# APP_1_DDR3_m.net
KiCad netlist of a schematic drawn in Altium Designer
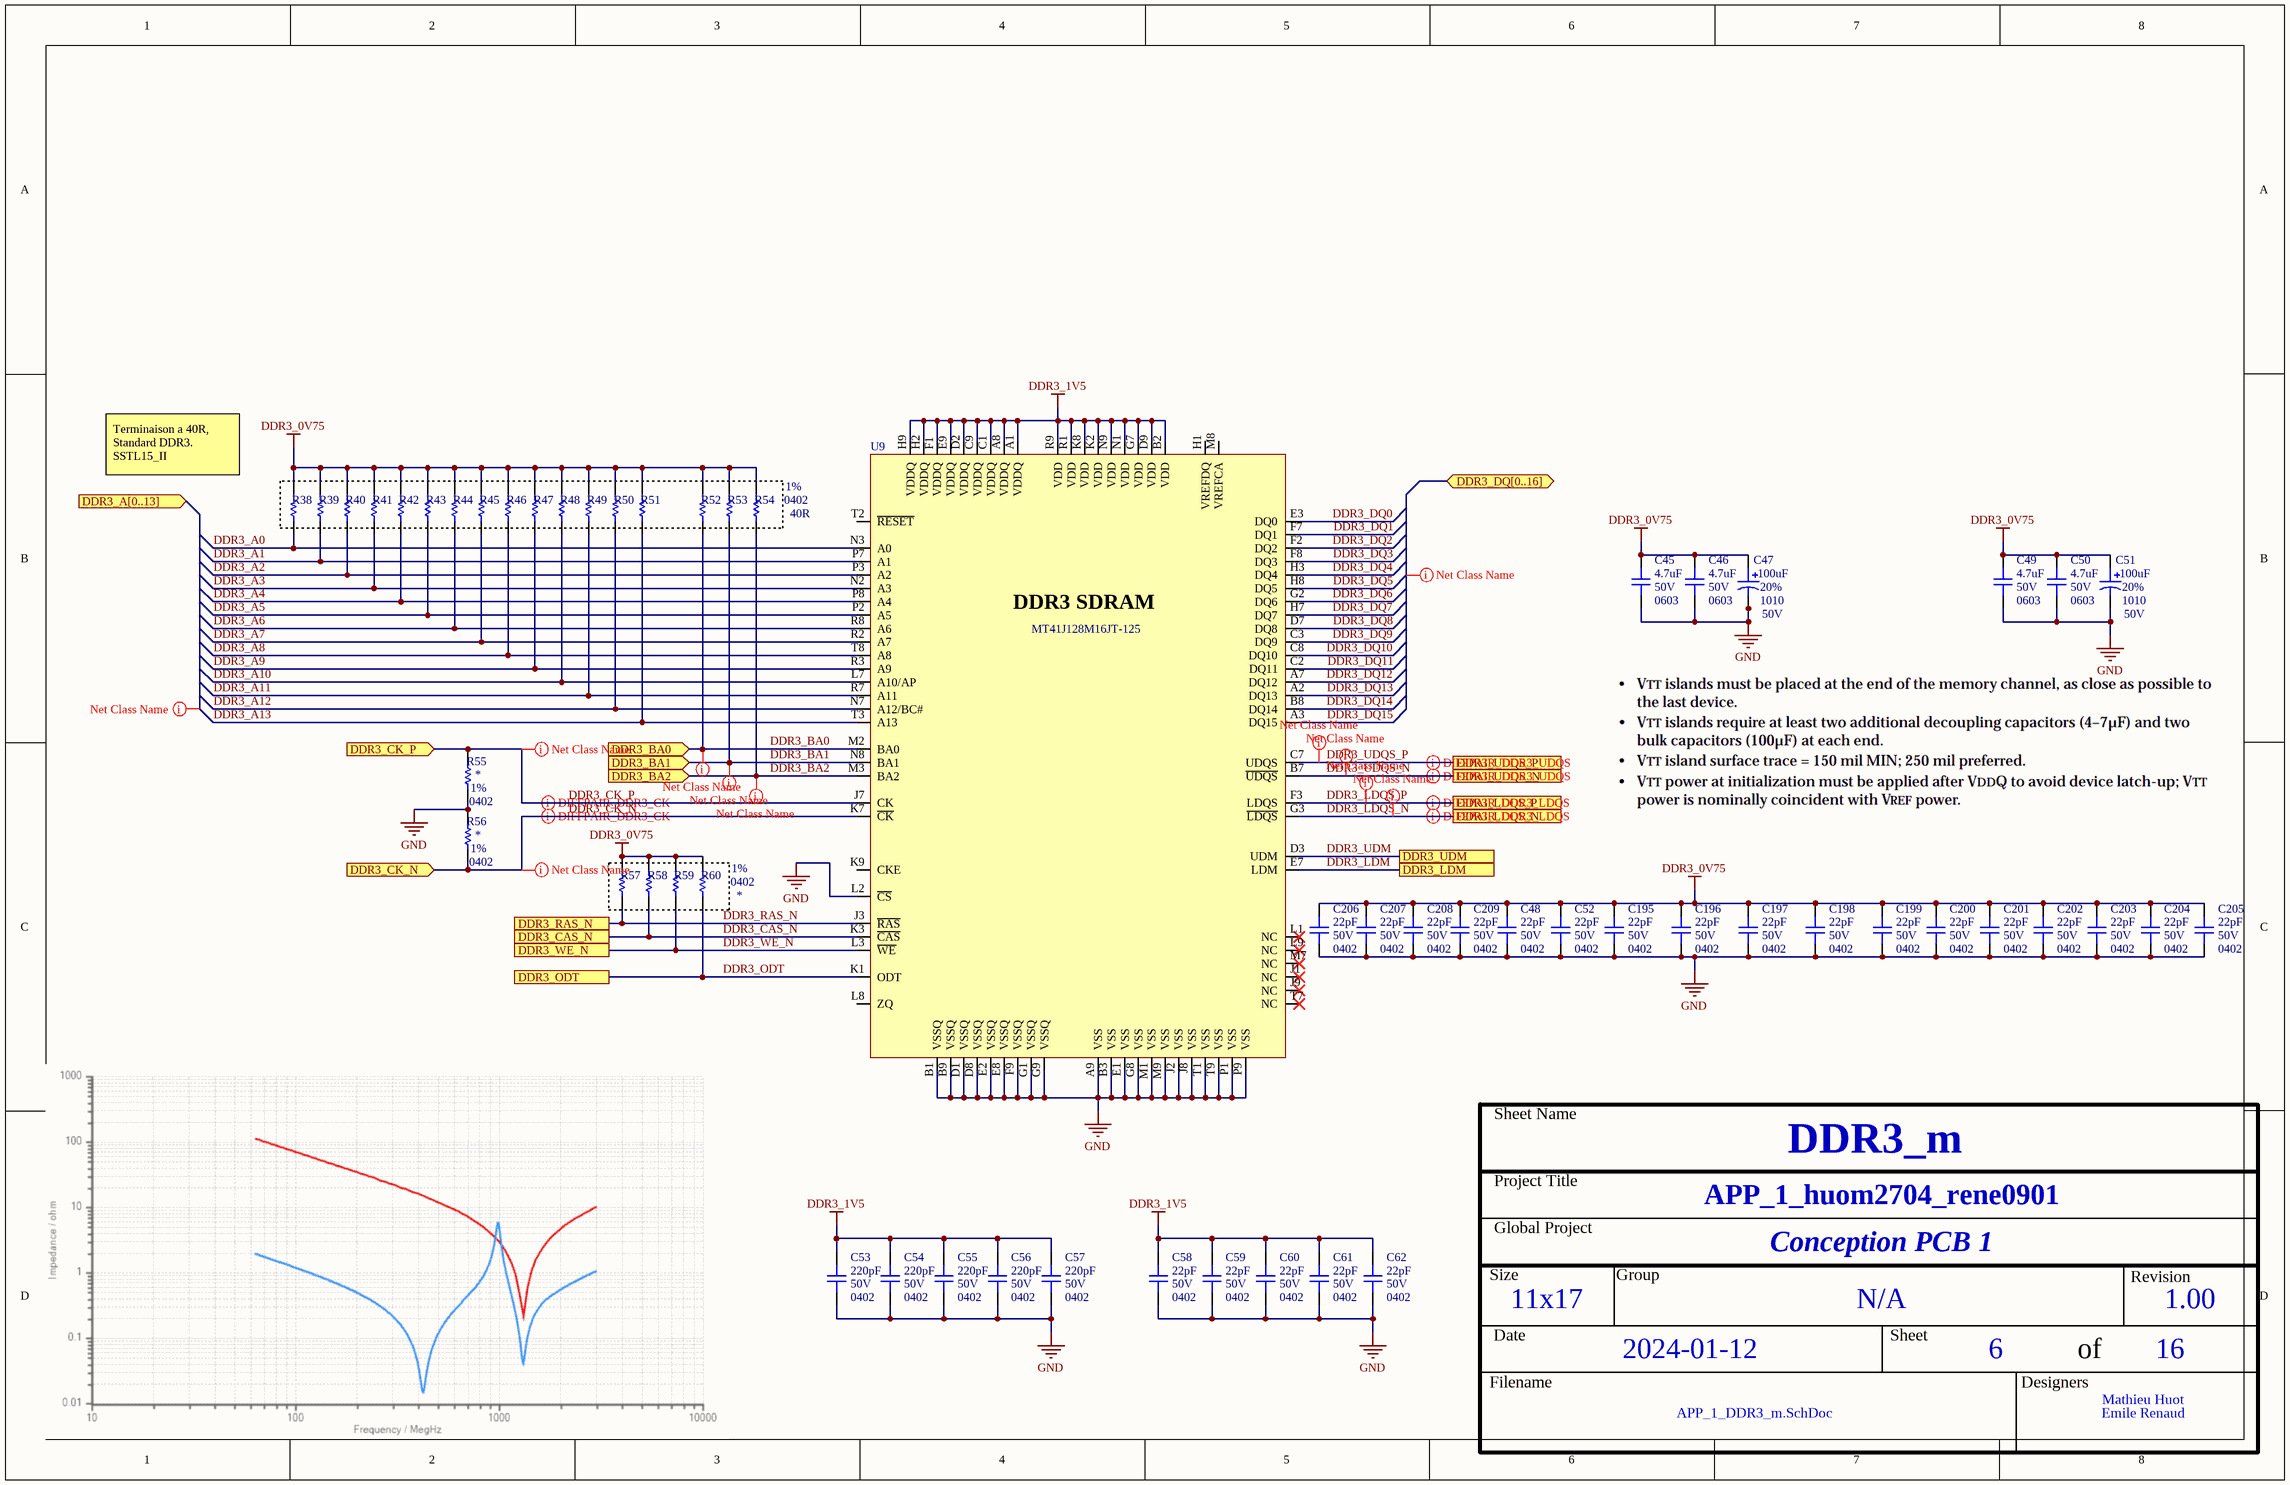
[diagram p0: APP_1_DDR3_m.SchDoc]

(export (version "E")
  (design (tool "Eeschema 10.0.6"))
  (components
    (comp (ref "C45")
      (value "4.7uF")
      (footprint "CAP_0603")
      (description "CAP - 0603")
      (fields
        (field (name "VOLTAGE") "50V")
        (field (name "PACKAGE") "0603")
        (field (name "CREATEDBY") "Jonathan Bouchard")
      )
      (libsource (lib "S7CAS_LIB2023") (part "CAP - 0603"))
    )
    (comp (ref "C46")
      (value "4.7uF")
      (footprint "CAP_0603")
      (description "CAP - 0603")
      (fields
        (field (name "VOLTAGE") "50V")
        (field (name "PACKAGE") "0603")
        (field (name "CREATEDBY") "Jonathan Bouchard")
      )
      (libsource (lib "S7CAS_LIB2023") (part "CAP - 0603"))
    )
    (comp (ref "C47")
      (value "100uF")
      (footprint "CAP_ALU_1010_vishay")
      (description "CAP - ALU 100uF 20% 50V - 1010")
      (fields
        (field (name "MFG") "Vishay Dale")
        (field (name "MFG PART NUMBER") "MAL215099101E3")
        (field (name "VOLTAGE") "50V")
        (field (name "PACKAGE") "1010")
        (field (name "PRECISION") "20%")
        (field (name "CREATEDBY") "Jonathan Bouchard")
      )
      (libsource (lib "S7CAS_LIB2023") (part "CAP_ALU_MAL215099101E3"))
    )
    (comp (ref "C48")
      (value "22pF")
      (footprint "CAP_0402")
      (description "CAP - 0402")
      (fields
        (field (name "VOLTAGE") "50V")
        (field (name "PACKAGE") "0402")
        (field (name "CREATEDBY") "Jonathan Bouchard")
      )
      (libsource (lib "S7CAS_LIB2023") (part "CAP - 0402"))
    )
    (comp (ref "C49")
      (value "4.7uF")
      (footprint "CAP_0603")
      (description "CAP - 0603")
      (fields
        (field (name "VOLTAGE") "50V")
        (field (name "PACKAGE") "0603")
        (field (name "CREATEDBY") "Jonathan Bouchard")
      )
      (libsource (lib "S7CAS_LIB2023") (part "CAP - 0603"))
    )
    (comp (ref "C50")
      (value "4.7uF")
      (footprint "CAP_0603")
      (description "CAP - 0603")
      (fields
        (field (name "VOLTAGE") "50V")
        (field (name "PACKAGE") "0603")
        (field (name "CREATEDBY") "Jonathan Bouchard")
      )
      (libsource (lib "S7CAS_LIB2023") (part "CAP - 0603"))
    )
    (comp (ref "C51")
      (value "100uF")
      (footprint "CAP_ALU_1010_vishay")
      (description "CAP - ALU 100uF 20% 50V - 1010")
      (fields
        (field (name "MFG") "Vishay Dale")
        (field (name "MFG PART NUMBER") "MAL215099101E3")
        (field (name "VOLTAGE") "50V")
        (field (name "PACKAGE") "1010")
        (field (name "PRECISION") "20%")
        (field (name "CREATEDBY") "Jonathan Bouchard")
      )
      (libsource (lib "S7CAS_LIB2023") (part "CAP_ALU_MAL215099101E3"))
    )
    (comp (ref "C52")
      (value "22pF")
      (footprint "CAP_0402")
      (description "CAP - 0402")
      (fields
        (field (name "VOLTAGE") "50V")
        (field (name "PACKAGE") "0402")
        (field (name "CREATEDBY") "Jonathan Bouchard")
      )
      (libsource (lib "S7CAS_LIB2023") (part "CAP - 0402"))
    )
    (comp (ref "C53")
      (value "220pF")
      (footprint "CAP_0402")
      (description "CAP - 0402")
      (fields
        (field (name "VOLTAGE") "50V")
        (field (name "PACKAGE") "0402")
        (field (name "CREATEDBY") "Jonathan Bouchard")
      )
      (libsource (lib "S7CAS_LIB2023") (part "CAP - 0402"))
    )
    (comp (ref "C54")
      (value "220pF")
      (footprint "CAP_0402")
      (description "CAP - 0402")
      (fields
        (field (name "VOLTAGE") "50V")
        (field (name "PACKAGE") "0402")
        (field (name "CREATEDBY") "Jonathan Bouchard")
      )
      (libsource (lib "S7CAS_LIB2023") (part "CAP - 0402"))
    )
    (comp (ref "C55")
      (value "220pF")
      (footprint "CAP_0402")
      (description "CAP - 0402")
      (fields
        (field (name "VOLTAGE") "50V")
        (field (name "PACKAGE") "0402")
        (field (name "CREATEDBY") "Jonathan Bouchard")
      )
      (libsource (lib "S7CAS_LIB2023") (part "CAP - 0402"))
    )
    (comp (ref "C56")
      (value "220pF")
      (footprint "CAP_0402")
      (description "CAP - 0402")
      (fields
        (field (name "VOLTAGE") "50V")
        (field (name "PACKAGE") "0402")
        (field (name "CREATEDBY") "Jonathan Bouchard")
      )
      (libsource (lib "S7CAS_LIB2023") (part "CAP - 0402"))
    )
    (comp (ref "C57")
      (value "220pF")
      (footprint "CAP_0402")
      (description "CAP - 0402")
      (fields
        (field (name "VOLTAGE") "50V")
        (field (name "PACKAGE") "0402")
        (field (name "CREATEDBY") "Jonathan Bouchard")
      )
      (libsource (lib "S7CAS_LIB2023") (part "CAP - 0402"))
    )
    (comp (ref "C58")
      (value "22pF")
      (footprint "CAP_0402")
      (description "CAP - 0402")
      (fields
        (field (name "VOLTAGE") "50V")
        (field (name "PACKAGE") "0402")
        (field (name "CREATEDBY") "Jonathan Bouchard")
      )
      (libsource (lib "S7CAS_LIB2023") (part "CAP - 0402"))
    )
    (comp (ref "C59")
      (value "22pF")
      (footprint "CAP_0402")
      (description "CAP - 0402")
      (fields
        (field (name "VOLTAGE") "50V")
        (field (name "PACKAGE") "0402")
        (field (name "CREATEDBY") "Jonathan Bouchard")
      )
      (libsource (lib "S7CAS_LIB2023") (part "CAP - 0402"))
    )
    (comp (ref "C60")
      (value "22pF")
      (footprint "CAP_0402")
      (description "CAP - 0402")
      (fields
        (field (name "VOLTAGE") "50V")
        (field (name "PACKAGE") "0402")
        (field (name "CREATEDBY") "Jonathan Bouchard")
      )
      (libsource (lib "S7CAS_LIB2023") (part "CAP - 0402"))
    )
    (comp (ref "C61")
      (value "22pF")
      (footprint "CAP_0402")
      (description "CAP - 0402")
      (fields
        (field (name "VOLTAGE") "50V")
        (field (name "PACKAGE") "0402")
        (field (name "CREATEDBY") "Jonathan Bouchard")
      )
      (libsource (lib "S7CAS_LIB2023") (part "CAP - 0402"))
    )
    (comp (ref "C62")
      (value "22pF")
      (footprint "CAP_0402")
      (description "CAP - 0402")
      (fields
        (field (name "VOLTAGE") "50V")
        (field (name "PACKAGE") "0402")
        (field (name "CREATEDBY") "Jonathan Bouchard")
      )
      (libsource (lib "S7CAS_LIB2023") (part "CAP - 0402"))
    )
    (comp (ref "C195")
      (value "22pF")
      (footprint "CAP_0402")
      (description "CAP - 0402")
      (fields
        (field (name "VOLTAGE") "50V")
        (field (name "PACKAGE") "0402")
        (field (name "CREATEDBY") "Jonathan Bouchard")
      )
      (libsource (lib "S7CAS_LIB2023") (part "CAP - 0402"))
    )
    (comp (ref "C196")
      (value "22pF")
      (footprint "CAP_0402")
      (description "CAP - 0402")
      (fields
        (field (name "VOLTAGE") "50V")
        (field (name "PACKAGE") "0402")
        (field (name "CREATEDBY") "Jonathan Bouchard")
      )
      (libsource (lib "S7CAS_LIB2023") (part "CAP - 0402"))
    )
    (comp (ref "C197")
      (value "22pF")
      (footprint "CAP_0402")
      (description "CAP - 0402")
      (fields
        (field (name "VOLTAGE") "50V")
        (field (name "PACKAGE") "0402")
        (field (name "CREATEDBY") "Jonathan Bouchard")
      )
      (libsource (lib "S7CAS_LIB2023") (part "CAP - 0402"))
    )
    (comp (ref "C198")
      (value "22pF")
      (footprint "CAP_0402")
      (description "CAP - 0402")
      (fields
        (field (name "VOLTAGE") "50V")
        (field (name "PACKAGE") "0402")
        (field (name "CREATEDBY") "Jonathan Bouchard")
      )
      (libsource (lib "S7CAS_LIB2023") (part "CAP - 0402"))
    )
    (comp (ref "C199")
      (value "22pF")
      (footprint "CAP_0402")
      (description "CAP - 0402")
      (fields
        (field (name "VOLTAGE") "50V")
        (field (name "PACKAGE") "0402")
        (field (name "CREATEDBY") "Jonathan Bouchard")
      )
      (libsource (lib "S7CAS_LIB2023") (part "CAP - 0402"))
    )
    (comp (ref "C200")
      (value "22pF")
      (footprint "CAP_0402")
      (description "CAP - 0402")
      (fields
        (field (name "VOLTAGE") "50V")
        (field (name "PACKAGE") "0402")
        (field (name "CREATEDBY") "Jonathan Bouchard")
      )
      (libsource (lib "S7CAS_LIB2023") (part "CAP - 0402"))
    )
    (comp (ref "C201")
      (value "22pF")
      (footprint "CAP_0402")
      (description "CAP - 0402")
      (fields
        (field (name "VOLTAGE") "50V")
        (field (name "PACKAGE") "0402")
        (field (name "CREATEDBY") "Jonathan Bouchard")
      )
      (libsource (lib "S7CAS_LIB2023") (part "CAP - 0402"))
    )
    (comp (ref "C202")
      (value "22pF")
      (footprint "CAP_0402")
      (description "CAP - 0402")
      (fields
        (field (name "VOLTAGE") "50V")
        (field (name "PACKAGE") "0402")
        (field (name "CREATEDBY") "Jonathan Bouchard")
      )
      (libsource (lib "S7CAS_LIB2023") (part "CAP - 0402"))
    )
    (comp (ref "C203")
      (value "22pF")
      (footprint "CAP_0402")
      (description "CAP - 0402")
      (fields
        (field (name "VOLTAGE") "50V")
        (field (name "PACKAGE") "0402")
        (field (name "CREATEDBY") "Jonathan Bouchard")
      )
      (libsource (lib "S7CAS_LIB2023") (part "CAP - 0402"))
    )
    (comp (ref "C204")
      (value "22pF")
      (footprint "CAP_0402")
      (description "CAP - 0402")
      (fields
        (field (name "VOLTAGE") "50V")
        (field (name "PACKAGE") "0402")
        (field (name "CREATEDBY") "Jonathan Bouchard")
      )
      (libsource (lib "S7CAS_LIB2023") (part "CAP - 0402"))
    )
    (comp (ref "C205")
      (value "22pF")
      (footprint "CAP_0402")
      (description "CAP - 0402")
      (fields
        (field (name "VOLTAGE") "50V")
        (field (name "PACKAGE") "0402")
        (field (name "CREATEDBY") "Jonathan Bouchard")
      )
      (libsource (lib "S7CAS_LIB2023") (part "CAP - 0402"))
    )
    (comp (ref "C206")
      (value "22pF")
      (footprint "CAP_0402")
      (description "CAP - 0402")
      (fields
        (field (name "VOLTAGE") "50V")
        (field (name "PACKAGE") "0402")
        (field (name "CREATEDBY") "Jonathan Bouchard")
      )
      (libsource (lib "S7CAS_LIB2023") (part "CAP - 0402"))
    )
    (comp (ref "C207")
      (value "22pF")
      (footprint "CAP_0402")
      (description "CAP - 0402")
      (fields
        (field (name "VOLTAGE") "50V")
        (field (name "PACKAGE") "0402")
        (field (name "CREATEDBY") "Jonathan Bouchard")
      )
      (libsource (lib "S7CAS_LIB2023") (part "CAP - 0402"))
    )
    (comp (ref "C208")
      (value "22pF")
      (footprint "CAP_0402")
      (description "CAP - 0402")
      (fields
        (field (name "VOLTAGE") "50V")
        (field (name "PACKAGE") "0402")
        (field (name "CREATEDBY") "Jonathan Bouchard")
      )
      (libsource (lib "S7CAS_LIB2023") (part "CAP - 0402"))
    )
    (comp (ref "C209")
      (value "22pF")
      (footprint "CAP_0402")
      (description "CAP - 0402")
      (fields
        (field (name "VOLTAGE") "50V")
        (field (name "PACKAGE") "0402")
        (field (name "CREATEDBY") "Jonathan Bouchard")
      )
      (libsource (lib "S7CAS_LIB2023") (part "CAP - 0402"))
    )
    (comp (ref "R38")
      (value "RES - 0402")
      (footprint "RES_0402")
      (fields
        (field (name "VOLTAGE") "50V")
        (field (name "POWER") "1/16W")
        (field (name "CREATEDBY") "Jonathan Bouchard")
      )
      (libsource (lib "S7CAS_LIB2023") (part "RES - 0402"))
    )
    (comp (ref "R39")
      (value "RES - 0402")
      (footprint "RES_0402")
      (fields
        (field (name "VOLTAGE") "50V")
        (field (name "POWER") "1/16W")
        (field (name "CREATEDBY") "Jonathan Bouchard")
      )
      (libsource (lib "S7CAS_LIB2023") (part "RES - 0402"))
    )
    (comp (ref "R40")
      (value "RES - 0402")
      (footprint "RES_0402")
      (fields
        (field (name "VOLTAGE") "50V")
        (field (name "POWER") "1/16W")
        (field (name "CREATEDBY") "Jonathan Bouchard")
      )
      (libsource (lib "S7CAS_LIB2023") (part "RES - 0402"))
    )
    (comp (ref "R41")
      (value "RES - 0402")
      (footprint "RES_0402")
      (fields
        (field (name "VOLTAGE") "50V")
        (field (name "POWER") "1/16W")
        (field (name "CREATEDBY") "Jonathan Bouchard")
      )
      (libsource (lib "S7CAS_LIB2023") (part "RES - 0402"))
    )
    (comp (ref "R42")
      (value "RES - 0402")
      (footprint "RES_0402")
      (fields
        (field (name "VOLTAGE") "50V")
        (field (name "POWER") "1/16W")
        (field (name "CREATEDBY") "Jonathan Bouchard")
      )
      (libsource (lib "S7CAS_LIB2023") (part "RES - 0402"))
    )
    (comp (ref "R43")
      (value "RES - 0402")
      (footprint "RES_0402")
      (fields
        (field (name "VOLTAGE") "50V")
        (field (name "POWER") "1/16W")
        (field (name "CREATEDBY") "Jonathan Bouchard")
      )
      (libsource (lib "S7CAS_LIB2023") (part "RES - 0402"))
    )
    (comp (ref "R44")
      (value "RES - 0402")
      (footprint "RES_0402")
      (fields
        (field (name "VOLTAGE") "50V")
        (field (name "POWER") "1/16W")
        (field (name "CREATEDBY") "Jonathan Bouchard")
      )
      (libsource (lib "S7CAS_LIB2023") (part "RES - 0402"))
    )
    (comp (ref "R45")
      (value "RES - 0402")
      (footprint "RES_0402")
      (fields
        (field (name "VOLTAGE") "50V")
        (field (name "POWER") "1/16W")
        (field (name "CREATEDBY") "Jonathan Bouchard")
      )
      (libsource (lib "S7CAS_LIB2023") (part "RES - 0402"))
    )
    (comp (ref "R46")
      (value "RES - 0402")
      (footprint "RES_0402")
      (fields
        (field (name "VOLTAGE") "50V")
        (field (name "POWER") "1/16W")
        (field (name "CREATEDBY") "Jonathan Bouchard")
      )
      (libsource (lib "S7CAS_LIB2023") (part "RES - 0402"))
    )
    (comp (ref "R47")
      (value "RES - 0402")
      (footprint "RES_0402")
      (fields
        (field (name "VOLTAGE") "50V")
        (field (name "POWER") "1/16W")
        (field (name "CREATEDBY") "Jonathan Bouchard")
      )
      (libsource (lib "S7CAS_LIB2023") (part "RES - 0402"))
    )
    (comp (ref "R48")
      (value "RES - 0402")
      (footprint "RES_0402")
      (fields
        (field (name "VOLTAGE") "50V")
        (field (name "POWER") "1/16W")
        (field (name "CREATEDBY") "Jonathan Bouchard")
      )
      (libsource (lib "S7CAS_LIB2023") (part "RES - 0402"))
    )
    (comp (ref "R49")
      (value "RES - 0402")
      (footprint "RES_0402")
      (fields
        (field (name "VOLTAGE") "50V")
        (field (name "POWER") "1/16W")
        (field (name "CREATEDBY") "Jonathan Bouchard")
      )
      (libsource (lib "S7CAS_LIB2023") (part "RES - 0402"))
    )
    (comp (ref "R50")
      (value "RES - 0402")
      (footprint "RES_0402")
      (fields
        (field (name "VOLTAGE") "50V")
        (field (name "POWER") "1/16W")
        (field (name "CREATEDBY") "Jonathan Bouchard")
      )
      (libsource (lib "S7CAS_LIB2023") (part "RES - 0402"))
    )
    (comp (ref "R51")
      (value "RES - 0402")
      (footprint "RES_0402")
      (fields
        (field (name "VOLTAGE") "50V")
        (field (name "POWER") "1/16W")
        (field (name "CREATEDBY") "Jonathan Bouchard")
      )
      (libsource (lib "S7CAS_LIB2023") (part "RES - 0402"))
    )
    (comp (ref "R52")
      (value "RES - 0402")
      (footprint "RES_0402")
      (fields
        (field (name "VOLTAGE") "50V")
        (field (name "POWER") "1/16W")
        (field (name "CREATEDBY") "Jonathan Bouchard")
      )
      (libsource (lib "S7CAS_LIB2023") (part "RES - 0402"))
    )
    (comp (ref "R53")
      (value "RES - 0402")
      (footprint "RES_0402")
      (fields
        (field (name "VOLTAGE") "50V")
        (field (name "POWER") "1/16W")
        (field (name "CREATEDBY") "Jonathan Bouchard")
      )
      (libsource (lib "S7CAS_LIB2023") (part "RES - 0402"))
    )
    (comp (ref "R54")
      (value "40R")
      (footprint "RES_0402")
      (description "RES - 0402")
      (fields
        (field (name "VOLTAGE") "50V")
        (field (name "POWER") "1/16W")
        (field (name "PACKAGE") "0402")
        (field (name "PRECISION") "1%")
        (field (name "CREATEDBY") "Jonathan Bouchard")
      )
      (libsource (lib "S7CAS_LIB2023") (part "RES - 0402"))
    )
    (comp (ref "R55")
      (value "RES - 0402")
      (footprint "RES_0402")
      (fields
        (field (name "VOLTAGE") "50V")
        (field (name "POWER") "1/16W")
        (field (name "PACKAGE") "0402")
        (field (name "PRECISION") "1%")
        (field (name "ALTIUM_VALUE") "*")
        (field (name "CREATEDBY") "Jonathan Bouchard")
      )
      (libsource (lib "S7CAS_LIB2023") (part "RES - 0402"))
    )
    (comp (ref "R56")
      (value "RES - 0402")
      (footprint "RES_0402")
      (fields
        (field (name "VOLTAGE") "50V")
        (field (name "POWER") "1/16W")
        (field (name "PACKAGE") "0402")
        (field (name "PRECISION") "1%")
        (field (name "ALTIUM_VALUE") "*")
        (field (name "CREATEDBY") "Jonathan Bouchard")
      )
      (libsource (lib "S7CAS_LIB2023") (part "RES - 0402"))
    )
    (comp (ref "R57")
      (value "RES - 0402")
      (footprint "RES_0402")
      (fields
        (field (name "VOLTAGE") "50V")
        (field (name "POWER") "1/16W")
        (field (name "CREATEDBY") "Jonathan Bouchard")
      )
      (libsource (lib "S7CAS_LIB2023") (part "RES - 0402"))
    )
    (comp (ref "R58")
      (value "RES - 0402")
      (footprint "RES_0402")
      (fields
        (field (name "VOLTAGE") "50V")
        (field (name "POWER") "1/16W")
        (field (name "CREATEDBY") "Jonathan Bouchard")
      )
      (libsource (lib "S7CAS_LIB2023") (part "RES - 0402"))
    )
    (comp (ref "R59")
      (value "RES - 0402")
      (footprint "RES_0402")
      (fields
        (field (name "VOLTAGE") "50V")
        (field (name "POWER") "1/16W")
        (field (name "CREATEDBY") "Jonathan Bouchard")
      )
      (libsource (lib "S7CAS_LIB2023") (part "RES - 0402"))
    )
    (comp (ref "R60")
      (value "RES - 0402")
      (footprint "RES_0402")
      (fields
        (field (name "VOLTAGE") "50V")
        (field (name "POWER") "1/16W")
        (field (name "PACKAGE") "0402")
        (field (name "PRECISION") "1%")
        (field (name "ALTIUM_VALUE") "*")
        (field (name "CREATEDBY") "Jonathan Bouchard")
      )
      (libsource (lib "S7CAS_LIB2023") (part "RES - 0402"))
    )
    (comp (ref "U9")
      (value "MT41J128M16JT-125")
      (footprint "MEM_DDR3_MT41J128M16JT-125")
      (description "MEM - DDR3 SDRAM 2GBIT 800MHZ - TFBGA-96")
      (fields
        (field (name "VOLTAGE") "1.425 V ~ 1.575 V")
        (field (name "MFG") "Micrel")
        (field (name "CREATEDBY") "Jonathan Bouchard")
      )
      (libsource (lib "S7CAS_LIB2023") (part "MEM_DDR3_MT41J128M16JT-125{colon}K TR"))
    )
  )
  (nets
    (net (code "2") (name "/DDR3_A0") (class "Default")
      (node (ref "R38") (pin "1") (pinfunction "1_1") (pintype "passive"))
      (node (ref "U9") (pin "N3") (pinfunction "A0_N3") (pintype "passive"))
    )
    (net (code "3") (name "/DDR3_A1") (class "Default")
      (node (ref "R39") (pin "1") (pinfunction "1_1") (pintype "passive"))
      (node (ref "U9") (pin "P7") (pinfunction "A1_P7") (pintype "passive"))
    )
    (net (code "4") (name "/DDR3_A2") (class "Default")
      (node (ref "R40") (pin "1") (pinfunction "1_1") (pintype "passive"))
      (node (ref "U9") (pin "P3") (pinfunction "A2_P3") (pintype "passive"))
    )
    (net (code "5") (name "/DDR3_A3") (class "Default")
      (node (ref "R41") (pin "1") (pinfunction "1_1") (pintype "passive"))
      (node (ref "U9") (pin "N2") (pinfunction "A3_N2") (pintype "passive"))
    )
    (net (code "6") (name "/DDR3_A4") (class "Default")
      (node (ref "R42") (pin "1") (pinfunction "1_1") (pintype "passive"))
      (node (ref "U9") (pin "P8") (pinfunction "A4_P8") (pintype "passive"))
    )
    (net (code "7") (name "/DDR3_A5") (class "Default")
      (node (ref "R43") (pin "1") (pinfunction "1_1") (pintype "passive"))
      (node (ref "U9") (pin "P2") (pinfunction "A5_P2") (pintype "passive"))
    )
    (net (code "8") (name "/DDR3_A6") (class "Default")
      (node (ref "R44") (pin "1") (pinfunction "1_1") (pintype "passive"))
      (node (ref "U9") (pin "R8") (pinfunction "A6_R8") (pintype "passive"))
    )
    (net (code "9") (name "/DDR3_A7") (class "Default")
      (node (ref "R45") (pin "1") (pinfunction "1_1") (pintype "passive"))
      (node (ref "U9") (pin "R2") (pinfunction "A7_R2") (pintype "passive"))
    )
    (net (code "10") (name "/DDR3_A8") (class "Default")
      (node (ref "R46") (pin "1") (pinfunction "1_1") (pintype "passive"))
      (node (ref "U9") (pin "T8") (pinfunction "A8_T8") (pintype "passive"))
    )
    (net (code "11") (name "/DDR3_A9") (class "Default")
      (node (ref "R47") (pin "1") (pinfunction "1_1") (pintype "passive"))
      (node (ref "U9") (pin "R3") (pinfunction "A9_R3") (pintype "passive"))
    )
    (net (code "12") (name "/DDR3_A10") (class "Default")
      (node (ref "R48") (pin "1") (pinfunction "1_1") (pintype "passive"))
      (node (ref "U9") (pin "L7") (pinfunction "A10/AP_L7") (pintype "passive"))
    )
    (net (code "13") (name "/DDR3_A11") (class "Default")
      (node (ref "R49") (pin "1") (pinfunction "1_1") (pintype "passive"))
      (node (ref "U9") (pin "R7") (pinfunction "A11_R7") (pintype "passive"))
    )
    (net (code "14") (name "/DDR3_A12") (class "Default")
      (node (ref "R50") (pin "1") (pinfunction "1_1") (pintype "passive"))
      (node (ref "U9") (pin "N7") (pinfunction "A12/BC#_N7") (pintype "passive"))
    )
    (net (code "15") (name "/DDR3_A13") (class "Default")
      (node (ref "R51") (pin "1") (pinfunction "1_1") (pintype "passive"))
      (node (ref "U9") (pin "T3") (pinfunction "A13_T3") (pintype "passive"))
    )
    (net (code "17") (name "/DDR3_BA0") (class "Default")
      (node (ref "R52") (pin "1") (pinfunction "1_1") (pintype "passive"))
      (node (ref "U9") (pin "M2") (pinfunction "BA0_M2") (pintype "passive"))
    )
    (net (code "18") (name "/DDR3_BA1") (class "Default")
      (node (ref "R53") (pin "1") (pinfunction "1_1") (pintype "passive"))
      (node (ref "U9") (pin "N8") (pinfunction "BA1_N8") (pintype "passive"))
    )
    (net (code "19") (name "/DDR3_BA2") (class "Default")
      (node (ref "R54") (pin "1") (pinfunction "1_1") (pintype "passive"))
      (node (ref "U9") (pin "M3") (pinfunction "BA2_M3") (pintype "passive"))
    )
    (net (code "20") (name "/DDR3_CAS_N") (class "Default")
      (node (ref "R58") (pin "1") (pinfunction "1_1") (pintype "passive"))
      (node (ref "U9") (pin "K3") (pinfunction "CAS_K3") (pintype "passive"))
    )
    (net (code "21") (name "/DDR3_CK_N") (class "Default")
      (node (ref "R56") (pin "1") (pinfunction "1_1") (pintype "passive"))
      (node (ref "U9") (pin "K7") (pinfunction "CK_K7") (pintype "passive"))
    )
    (net (code "22") (name "/DDR3_CK_P") (class "Default")
      (node (ref "R55") (pin "2") (pinfunction "2_2") (pintype "passive"))
      (node (ref "U9") (pin "J7") (pinfunction "CK_J7") (pintype "passive"))
    )
    (net (code "23") (name "/DDR3_DQ0") (class "Default")
      (node (ref "U9") (pin "E3") (pinfunction "DQ0_E3") (pintype "passive"))
    )
    (net (code "24") (name "/DDR3_DQ1") (class "Default")
      (node (ref "U9") (pin "F7") (pinfunction "DQ1_F7") (pintype "passive"))
    )
    (net (code "25") (name "/DDR3_DQ2") (class "Default")
      (node (ref "U9") (pin "F2") (pinfunction "DQ2_F2") (pintype "passive"))
    )
    (net (code "26") (name "/DDR3_DQ3") (class "Default")
      (node (ref "U9") (pin "F8") (pinfunction "DQ3_F8") (pintype "passive"))
    )
    (net (code "27") (name "/DDR3_DQ4") (class "Default")
      (node (ref "U9") (pin "H3") (pinfunction "DQ4_H3") (pintype "passive"))
    )
    (net (code "28") (name "/DDR3_DQ5") (class "Default")
      (node (ref "U9") (pin "H8") (pinfunction "DQ5_H8") (pintype "passive"))
    )
    (net (code "29") (name "/DDR3_DQ6") (class "Default")
      (node (ref "U9") (pin "G2") (pinfunction "DQ6_G2") (pintype "passive"))
    )
    (net (code "30") (name "/DDR3_DQ7") (class "Default")
      (node (ref "U9") (pin "H7") (pinfunction "DQ7_H7") (pintype "passive"))
    )
    (net (code "31") (name "/DDR3_DQ8") (class "Default")
      (node (ref "U9") (pin "D7") (pinfunction "DQ8_D7") (pintype "passive"))
    )
    (net (code "32") (name "/DDR3_DQ9") (class "Default")
      (node (ref "U9") (pin "C3") (pinfunction "DQ9_C3") (pintype "passive"))
    )
    (net (code "33") (name "/DDR3_DQ10") (class "Default")
      (node (ref "U9") (pin "C8") (pinfunction "DQ10_C8") (pintype "passive"))
    )
    (net (code "34") (name "/DDR3_DQ11") (class "Default")
      (node (ref "U9") (pin "C2") (pinfunction "DQ11_C2") (pintype "passive"))
    )
    (net (code "35") (name "/DDR3_DQ12") (class "Default")
      (node (ref "U9") (pin "A7") (pinfunction "DQ12_A7") (pintype "passive"))
    )
    (net (code "36") (name "/DDR3_DQ13") (class "Default")
      (node (ref "U9") (pin "A2") (pinfunction "DQ13_A2") (pintype "passive"))
    )
    (net (code "37") (name "/DDR3_DQ14") (class "Default")
      (node (ref "U9") (pin "B8") (pinfunction "DQ14_B8") (pintype "passive"))
    )
    (net (code "38") (name "/DDR3_DQ15") (class "Default")
      (node (ref "U9") (pin "A3") (pinfunction "DQ15_A3") (pintype "passive"))
    )
    (net (code "40") (name "/DDR3_LDM") (class "Default")
      (node (ref "U9") (pin "E7") (pinfunction "LDM_E7") (pintype "passive"))
    )
    (net (code "41") (name "/DDR3_LDQS_N") (class "Default")
      (node (ref "U9") (pin "G3") (pinfunction "LDQS_G3") (pintype "passive"))
    )
    (net (code "42") (name "/DDR3_LDQS_P") (class "Default")
      (node (ref "U9") (pin "F3") (pinfunction "LDQS_F3") (pintype "passive"))
    )
    (net (code "43") (name "/DDR3_ODT") (class "Default")
      (node (ref "R60") (pin "1") (pinfunction "1_1") (pintype "passive"))
      (node (ref "U9") (pin "K1") (pinfunction "ODT_K1") (pintype "passive"))
    )
    (net (code "44") (name "/DDR3_RAS_N") (class "Default")
      (node (ref "R57") (pin "1") (pinfunction "1_1") (pintype "passive"))
      (node (ref "U9") (pin "J3") (pinfunction "RAS_J3") (pintype "passive"))
    )
    (net (code "45") (name "/DDR3_UDM") (class "Default")
      (node (ref "U9") (pin "D3") (pinfunction "UDM_D3") (pintype "passive"))
    )
    (net (code "46") (name "/DDR3_UDQS_N") (class "Default")
      (node (ref "U9") (pin "B7") (pinfunction "UDQS_B7") (pintype "passive"))
    )
    (net (code "47") (name "/DDR3_UDQS_P") (class "Default")
      (node (ref "U9") (pin "C7") (pinfunction "UDQS_C7") (pintype "passive"))
    )
    (net (code "48") (name "/DDR3_WE_N") (class "Default")
      (node (ref "R59") (pin "1") (pinfunction "1_1") (pintype "passive"))
      (node (ref "U9") (pin "L3") (pinfunction "WE_L3") (pintype "passive"))
    )
    (net (code "49") (name "DDR3_0V75") (class "Default")
      (node (ref "C195") (pin "2") (pinfunction "2_2") (pintype "passive"))
      (node (ref "C196") (pin "2") (pinfunction "2_2") (pintype "passive"))
      (node (ref "C197") (pin "2") (pinfunction "2_2") (pintype "passive"))
      (node (ref "C198") (pin "2") (pinfunction "2_2") (pintype "passive"))
      (node (ref "C199") (pin "2") (pinfunction "2_2") (pintype "passive"))
      (node (ref "C200") (pin "2") (pinfunction "2_2") (pintype "passive"))
      (node (ref "C201") (pin "2") (pinfunction "2_2") (pintype "passive"))
      (node (ref "C202") (pin "2") (pinfunction "2_2") (pintype "passive"))
      (node (ref "C203") (pin "2") (pinfunction "2_2") (pintype "passive"))
      (node (ref "C204") (pin "2") (pinfunction "2_2") (pintype "passive"))
      (node (ref "C205") (pin "2") (pinfunction "2_2") (pintype "passive"))
      (node (ref "C206") (pin "2") (pinfunction "2_2") (pintype "passive"))
      (node (ref "C207") (pin "2") (pinfunction "2_2") (pintype "passive"))
      (node (ref "C208") (pin "2") (pinfunction "2_2") (pintype "passive"))
      (node (ref "C209") (pin "2") (pinfunction "2_2") (pintype "passive"))
      (node (ref "C45") (pin "2") (pinfunction "2_2") (pintype "passive"))
      (node (ref "C46") (pin "2") (pinfunction "2_2") (pintype "passive"))
      (node (ref "C47") (pin "1") (pinfunction "1_1") (pintype "passive"))
      (node (ref "C48") (pin "2") (pinfunction "2_2") (pintype "passive"))
      (node (ref "C49") (pin "2") (pinfunction "2_2") (pintype "passive"))
      (node (ref "C50") (pin "2") (pinfunction "2_2") (pintype "passive"))
      (node (ref "C51") (pin "1") (pinfunction "1_1") (pintype "passive"))
      (node (ref "C52") (pin "2") (pinfunction "2_2") (pintype "passive"))
      (node (ref "R38") (pin "2") (pinfunction "2_2") (pintype "passive"))
      (node (ref "R39") (pin "2") (pinfunction "2_2") (pintype "passive"))
      (node (ref "R40") (pin "2") (pinfunction "2_2") (pintype "passive"))
      (node (ref "R41") (pin "2") (pinfunction "2_2") (pintype "passive"))
      (node (ref "R42") (pin "2") (pinfunction "2_2") (pintype "passive"))
      (node (ref "R43") (pin "2") (pinfunction "2_2") (pintype "passive"))
      (node (ref "R44") (pin "2") (pinfunction "2_2") (pintype "passive"))
      (node (ref "R45") (pin "2") (pinfunction "2_2") (pintype "passive"))
      (node (ref "R46") (pin "2") (pinfunction "2_2") (pintype "passive"))
      (node (ref "R47") (pin "2") (pinfunction "2_2") (pintype "passive"))
      (node (ref "R48") (pin "2") (pinfunction "2_2") (pintype "passive"))
      (node (ref "R49") (pin "2") (pinfunction "2_2") (pintype "passive"))
      (node (ref "R50") (pin "2") (pinfunction "2_2") (pintype "passive"))
      (node (ref "R51") (pin "2") (pinfunction "2_2") (pintype "passive"))
      (node (ref "R52") (pin "2") (pinfunction "2_2") (pintype "passive"))
      (node (ref "R53") (pin "2") (pinfunction "2_2") (pintype "passive"))
      (node (ref "R54") (pin "2") (pinfunction "2_2") (pintype "passive"))
      (node (ref "R57") (pin "2") (pinfunction "2_2") (pintype "passive"))
      (node (ref "R58") (pin "2") (pinfunction "2_2") (pintype "passive"))
      (node (ref "R59") (pin "2") (pinfunction "2_2") (pintype "passive"))
      (node (ref "R60") (pin "2") (pinfunction "2_2") (pintype "passive"))
    )
    (net (code "50") (name "DDR3_1V5") (class "Default")
      (node (ref "C53") (pin "2") (pinfunction "2_2") (pintype "passive"))
      (node (ref "C54") (pin "2") (pinfunction "2_2") (pintype "passive"))
      (node (ref "C55") (pin "2") (pinfunction "2_2") (pintype "passive"))
      (node (ref "C56") (pin "2") (pinfunction "2_2") (pintype "passive"))
      (node (ref "C57") (pin "2") (pinfunction "2_2") (pintype "passive"))
      (node (ref "C58") (pin "2") (pinfunction "2_2") (pintype "passive"))
      (node (ref "C59") (pin "2") (pinfunction "2_2") (pintype "passive"))
      (node (ref "C60") (pin "2") (pinfunction "2_2") (pintype "passive"))
      (node (ref "C61") (pin "2") (pinfunction "2_2") (pintype "passive"))
      (node (ref "C62") (pin "2") (pinfunction "2_2") (pintype "passive"))
      (node (ref "U9") (pin "A1") (pinfunction "VDDQ_A1") (pintype "passive"))
      (node (ref "U9") (pin "A8") (pinfunction "VDDQ_A8") (pintype "passive"))
      (node (ref "U9") (pin "B2") (pinfunction "VDD_B2") (pintype "passive"))
      (node (ref "U9") (pin "C1") (pinfunction "VDDQ_C1") (pintype "passive"))
      (node (ref "U9") (pin "C9") (pinfunction "VDDQ_C9") (pintype "passive"))
      (node (ref "U9") (pin "D2") (pinfunction "VDDQ_D2") (pintype "passive"))
      (node (ref "U9") (pin "D9") (pinfunction "VDD_D9") (pintype "passive"))
      (node (ref "U9") (pin "E9") (pinfunction "VDDQ_E9") (pintype "passive"))
      (node (ref "U9") (pin "F1") (pinfunction "VDDQ_F1") (pintype "passive"))
      (node (ref "U9") (pin "G7") (pinfunction "VDD_G7") (pintype "passive"))
      (node (ref "U9") (pin "H2") (pinfunction "VDDQ_H2") (pintype "passive"))
      (node (ref "U9") (pin "H9") (pinfunction "VDDQ_H9") (pintype "passive"))
      (node (ref "U9") (pin "K2") (pinfunction "VDD_K2") (pintype "passive"))
      (node (ref "U9") (pin "K8") (pinfunction "VDD_K8") (pintype "passive"))
      (node (ref "U9") (pin "N1") (pinfunction "VDD_N1") (pintype "passive"))
      (node (ref "U9") (pin "N9") (pinfunction "VDD_N9") (pintype "passive"))
      (node (ref "U9") (pin "R1") (pinfunction "VDD_R1") (pintype "passive"))
      (node (ref "U9") (pin "R9") (pinfunction "VDD_R9") (pintype "passive"))
    )
    (net (code "51") (name "GND") (class "Default")
      (node (ref "C195") (pin "1") (pinfunction "1_1") (pintype "passive"))
      (node (ref "C196") (pin "1") (pinfunction "1_1") (pintype "passive"))
      (node (ref "C197") (pin "1") (pinfunction "1_1") (pintype "passive"))
      (node (ref "C198") (pin "1") (pinfunction "1_1") (pintype "passive"))
      (node (ref "C199") (pin "1") (pinfunction "1_1") (pintype "passive"))
      (node (ref "C200") (pin "1") (pinfunction "1_1") (pintype "passive"))
      (node (ref "C201") (pin "1") (pinfunction "1_1") (pintype "passive"))
      (node (ref "C202") (pin "1") (pinfunction "1_1") (pintype "passive"))
      (node (ref "C203") (pin "1") (pinfunction "1_1") (pintype "passive"))
      (node (ref "C204") (pin "1") (pinfunction "1_1") (pintype "passive"))
      (node (ref "C205") (pin "1") (pinfunction "1_1") (pintype "passive"))
      (node (ref "C206") (pin "1") (pinfunction "1_1") (pintype "passive"))
      (node (ref "C207") (pin "1") (pinfunction "1_1") (pintype "passive"))
      (node (ref "C208") (pin "1") (pinfunction "1_1") (pintype "passive"))
      (node (ref "C209") (pin "1") (pinfunction "1_1") (pintype "passive"))
      (node (ref "C45") (pin "1") (pinfunction "1_1") (pintype "passive"))
      (node (ref "C46") (pin "1") (pinfunction "1_1") (pintype "passive"))
      (node (ref "C47") (pin "2") (pinfunction "2_2") (pintype "passive"))
      (node (ref "C48") (pin "1") (pinfunction "1_1") (pintype "passive"))
      (node (ref "C49") (pin "1") (pinfunction "1_1") (pintype "passive"))
      (node (ref "C50") (pin "1") (pinfunction "1_1") (pintype "passive"))
      (node (ref "C51") (pin "2") (pinfunction "2_2") (pintype "passive"))
      (node (ref "C52") (pin "1") (pinfunction "1_1") (pintype "passive"))
      (node (ref "C53") (pin "1") (pinfunction "1_1") (pintype "passive"))
      (node (ref "C54") (pin "1") (pinfunction "1_1") (pintype "passive"))
      (node (ref "C55") (pin "1") (pinfunction "1_1") (pintype "passive"))
      (node (ref "C56") (pin "1") (pinfunction "1_1") (pintype "passive"))
      (node (ref "C57") (pin "1") (pinfunction "1_1") (pintype "passive"))
      (node (ref "C58") (pin "1") (pinfunction "1_1") (pintype "passive"))
      (node (ref "C59") (pin "1") (pinfunction "1_1") (pintype "passive"))
      (node (ref "C60") (pin "1") (pinfunction "1_1") (pintype "passive"))
      (node (ref "C61") (pin "1") (pinfunction "1_1") (pintype "passive"))
      (node (ref "C62") (pin "1") (pinfunction "1_1") (pintype "passive"))
      (node (ref "R55") (pin "1") (pinfunction "1_1") (pintype "passive"))
      (node (ref "R56") (pin "2") (pinfunction "2_2") (pintype "passive"))
      (node (ref "U9") (pin "A9") (pinfunction "VSS_A9") (pintype "passive"))
      (node (ref "U9") (pin "B1") (pinfunction "VSSQ_B1") (pintype "passive"))
      (node (ref "U9") (pin "B3") (pinfunction "VSS_B3") (pintype "passive"))
      (node (ref "U9") (pin "B9") (pinfunction "VSSQ_B9") (pintype "passive"))
      (node (ref "U9") (pin "D1") (pinfunction "VSSQ_D1") (pintype "passive"))
      (node (ref "U9") (pin "D8") (pinfunction "VSSQ_D8") (pintype "passive"))
      (node (ref "U9") (pin "E1") (pinfunction "VSS_E1") (pintype "passive"))
      (node (ref "U9") (pin "E2") (pinfunction "VSSQ_E2") (pintype "passive"))
      (node (ref "U9") (pin "E8") (pinfunction "VSSQ_E8") (pintype "passive"))
      (node (ref "U9") (pin "F9") (pinfunction "VSSQ_F9") (pintype "passive"))
      (node (ref "U9") (pin "G1") (pinfunction "VSSQ_G1") (pintype "passive"))
      (node (ref "U9") (pin "G8") (pinfunction "VSS_G8") (pintype "passive"))
      (node (ref "U9") (pin "G9") (pinfunction "VSSQ_G9") (pintype "passive"))
      (node (ref "U9") (pin "J2") (pinfunction "VSS_J2") (pintype "passive"))
      (node (ref "U9") (pin "J8") (pinfunction "VSS_J8") (pintype "passive"))
      (node (ref "U9") (pin "L2") (pinfunction "CS_L2") (pintype "passive"))
      (node (ref "U9") (pin "M1") (pinfunction "VSS_M1") (pintype "passive"))
      (node (ref "U9") (pin "M9") (pinfunction "VSS_M9") (pintype "passive"))
      (node (ref "U9") (pin "P1") (pinfunction "VSS_P1") (pintype "passive"))
      (node (ref "U9") (pin "P9") (pinfunction "VSS_P9") (pintype "passive"))
      (node (ref "U9") (pin "T1") (pinfunction "VSS_T1") (pintype "passive"))
      (node (ref "U9") (pin "T9") (pinfunction "VSS_T9") (pintype "passive"))
    )
    (net (code "52") (name "unconnected-(U9-CKE-PadK9)") (class "Default")
      (node (ref "U9") (pin "K9") (pinfunction "CKE_K9") (pintype "passive"))
    )
    (net (code "53") (name "unconnected-(U9-NC-PadJ1)") (class "Default")
      (node (ref "U9") (pin "J1") (pinfunction "NC_J1") (pintype "passive+no_connect"))
    )
    (net (code "54") (name "unconnected-(U9-NC-PadJ9)") (class "Default")
      (node (ref "U9") (pin "J9") (pinfunction "NC_J9") (pintype "passive+no_connect"))
    )
    (net (code "55") (name "unconnected-(U9-NC-PadL1)") (class "Default")
      (node (ref "U9") (pin "L1") (pinfunction "NC_L1") (pintype "passive+no_connect"))
    )
    (net (code "56") (name "unconnected-(U9-NC-PadL9)") (class "Default")
      (node (ref "U9") (pin "L9") (pinfunction "NC_L9") (pintype "passive+no_connect"))
    )
    (net (code "57") (name "unconnected-(U9-NC-PadM7)") (class "Default")
      (node (ref "U9") (pin "M7") (pinfunction "NC_M7") (pintype "passive+no_connect"))
    )
    (net (code "58") (name "unconnected-(U9-NC-PadT7)") (class "Default")
      (node (ref "U9") (pin "T7") (pinfunction "NC_T7") (pintype "passive+no_connect"))
    )
    (net (code "59") (name "unconnected-(U9-RESET-PadT2)") (class "Default")
      (node (ref "U9") (pin "T2") (pinfunction "RESET_T2") (pintype "passive"))
    )
    (net (code "60") (name "unconnected-(U9-VREFCA-PadM8)") (class "Default")
      (node (ref "U9") (pin "M8") (pinfunction "VREFCA_M8") (pintype "passive"))
    )
    (net (code "61") (name "unconnected-(U9-VREFDQ-PadH1)") (class "Default")
      (node (ref "U9") (pin "H1") (pinfunction "VREFDQ_H1") (pintype "passive"))
    )
    (net (code "62") (name "unconnected-(U9-ZQ-PadL8)") (class "Default")
      (node (ref "U9") (pin "L8") (pinfunction "ZQ_L8") (pintype "passive"))
    )
  )
)
